# Controller.net
KiCad netlist of a schematic drawn in EAGLE
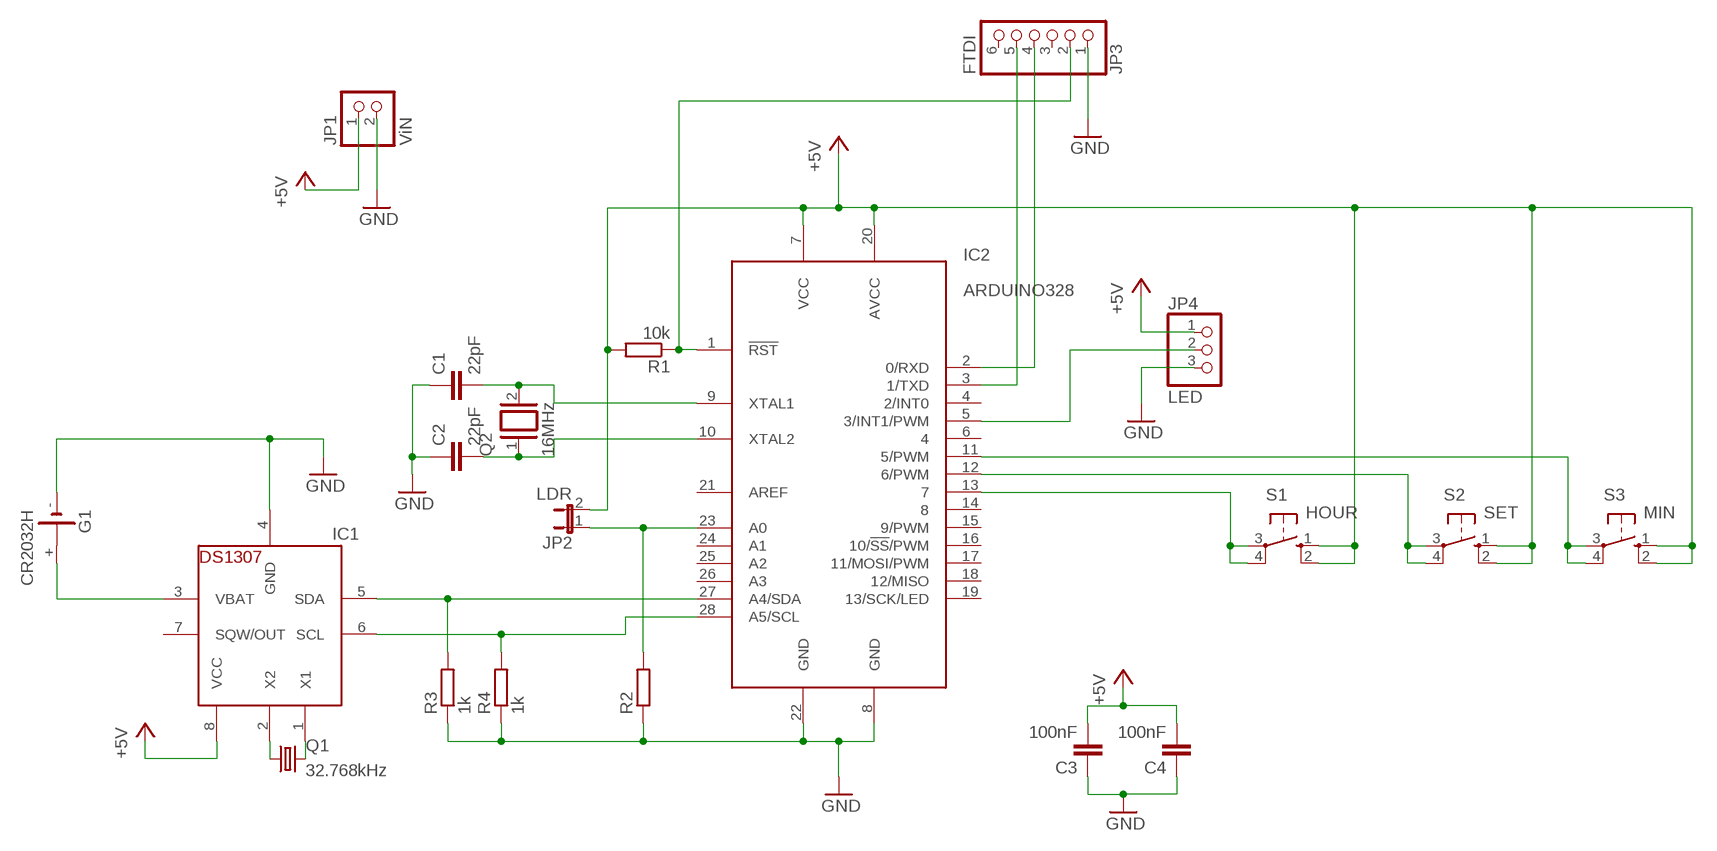
[diagram p0: schematic, sheet 1]

(export (version "E")
  (design (tool "Eeschema 10.0.6"))
  (components
    (comp (ref "C1")
      (value "22pF")
      (footprint "eagle-import:C025-024X044")
      (libsource (lib "eagle-import") (part "C-EU025-024X044"))
    )
    (comp (ref "C2")
      (value "22pF")
      (footprint "eagle-import:C025-024X044")
      (libsource (lib "eagle-import") (part "C-EU025-024X044"))
    )
    (comp (ref "C3")
      (value "100nF")
      (footprint "eagle-import:C025-024X044")
      (libsource (lib "eagle-import") (part "C-EU025-024X044"))
    )
    (comp (ref "C4")
      (value "100nF")
      (footprint "eagle-import:C025-024X044")
      (libsource (lib "eagle-import") (part "C-EU025-024X044"))
    )
    (comp (ref "G1")
      (value "CR2032H")
      (footprint "eagle-import:CR2032H")
      (libsource (lib "eagle-import") (part "CR2032H"))
    )
    (comp (ref "IC1")
      (value "DS1307")
      (footprint "eagle-import:DIL08")
      (libsource (lib "eagle-import") (part "DS1307"))
    )
    (comp (ref "IC2")
      (value "ARDUINO328")
      (footprint "eagle-import:DIP28")
      (libsource (lib "eagle-import") (part "ARDUINO328"))
    )
    (comp (ref "JP1")
      (value "ViN")
      (footprint "eagle-import:1X02")
      (libsource (lib "eagle-import") (part "PINHD-1X2"))
    )
    (comp (ref "JP2")
      (value "LDR")
      (footprint "eagle-import:JP1")
      (libsource (lib "eagle-import") (part "JP1E"))
    )
    (comp (ref "JP3")
      (value "FTDI")
      (footprint "eagle-import:1X06")
      (libsource (lib "eagle-import") (part "PINHD-1X6"))
    )
    (comp (ref "JP4")
      (value "LED")
      (footprint "eagle-import:1X03")
      (libsource (lib "eagle-import") (part "PINHD-1X3"))
    )
    (comp (ref "Q1")
      (value "32.768kHz")
      (footprint "eagle-import:TC26V")
      (libsource (lib "eagle-import") (part "CRYSTALTC26V"))
    )
    (comp (ref "Q2")
      (value "16MHz")
      (footprint "eagle-import:QS")
      (libsource (lib "eagle-import") (part "XTAL/S"))
    )
    (comp (ref "R1")
      (value "10k")
      (footprint "eagle-import:0204_5")
      (libsource (lib "eagle-import") (part "R-EU_0204/5"))
    )
    (comp (ref "R2")
      (value "R-EU_0204/5")
      (footprint "eagle-import:0204_5")
      (libsource (lib "eagle-import") (part "R-EU_0204/5"))
    )
    (comp (ref "R3")
      (value "1k")
      (footprint "eagle-import:0204_5")
      (libsource (lib "eagle-import") (part "R-EU_0204/5"))
    )
    (comp (ref "R4")
      (value "1k")
      (footprint "eagle-import:0204_5")
      (libsource (lib "eagle-import") (part "R-EU_0204/5"))
    )
    (comp (ref "S1")
      (value "HOUR")
      (footprint "eagle-import:B3F-10XX")
      (fields (field (name "MPN") "B3F-1000"))
      (libsource (lib "eagle-import") (part "10-XX"))
    )
    (comp (ref "S2")
      (value "SET")
      (footprint "eagle-import:B3F-10XX")
      (fields (field (name "MPN") "B3F-1000"))
      (libsource (lib "eagle-import") (part "10-XX"))
    )
    (comp (ref "S3")
      (value "MIN")
      (footprint "eagle-import:B3F-10XX")
      (fields (field (name "MPN") "B3F-1000"))
      (libsource (lib "eagle-import") (part "10-XX"))
    )
  )
  (nets
    (net (code "1") (name "+5V") (class "Default")
      (node (ref "C3") (pin "2") (pinfunction "2_2") (pintype "passive"))
      (node (ref "C4") (pin "2") (pinfunction "2_2") (pintype "passive"))
      (node (ref "IC1") (pin "8") (pinfunction "VCC_8") (pintype "power_in"))
      (node (ref "IC2") (pin "20") (pinfunction "AVCC_20") (pintype "bidirectional"))
      (node (ref "IC2") (pin "7") (pinfunction "VCC_7") (pintype "bidirectional"))
      (node (ref "JP1") (pin "1") (pinfunction "1_1") (pintype "passive"))
      (node (ref "JP2") (pin "2") (pinfunction "2_2") (pintype "passive"))
      (node (ref "JP4") (pin "1") (pinfunction "1_1") (pintype "passive"))
      (node (ref "R1") (pin "2") (pinfunction "2_2") (pintype "passive"))
      (node (ref "S1") (pin "1") (pinfunction "S_1") (pintype "passive"))
      (node (ref "S1") (pin "2") (pinfunction "S1_2") (pintype "passive"))
      (node (ref "S2") (pin "1") (pinfunction "S_1") (pintype "passive"))
      (node (ref "S2") (pin "2") (pinfunction "S1_2") (pintype "passive"))
      (node (ref "S3") (pin "1") (pinfunction "S_1") (pintype "passive"))
      (node (ref "S3") (pin "2") (pinfunction "S1_2") (pintype "passive"))
    )
    (net (code "2") (name "GND") (class "Default")
      (node (ref "C1") (pin "1") (pinfunction "1_1") (pintype "passive"))
      (node (ref "C2") (pin "1") (pinfunction "1_1") (pintype "passive"))
      (node (ref "C3") (pin "1") (pinfunction "1_1") (pintype "passive"))
      (node (ref "C4") (pin "1") (pinfunction "1_1") (pintype "passive"))
      (node (ref "G1") (pin "-") (pinfunction "-_-") (pintype "passive"))
      (node (ref "IC1") (pin "4") (pinfunction "GND_4") (pintype "power_in"))
      (node (ref "IC2") (pin "22") (pinfunction "GND_22") (pintype "bidirectional"))
      (node (ref "IC2") (pin "8") (pinfunction "GND_8") (pintype "bidirectional"))
      (node (ref "JP1") (pin "2") (pinfunction "2_2") (pintype "passive"))
      (node (ref "JP3") (pin "1") (pinfunction "1_1") (pintype "passive"))
      (node (ref "JP4") (pin "3") (pinfunction "3_3") (pintype "passive"))
      (node (ref "R2") (pin "1") (pinfunction "1_1") (pintype "passive"))
      (node (ref "R3") (pin "1") (pinfunction "1_1") (pintype "passive"))
      (node (ref "R4") (pin "1") (pinfunction "1_1") (pintype "passive"))
    )
    (net (code "3") (name "Net-(IC1-SCL)") (class "Default")
      (node (ref "IC1") (pin "6") (pinfunction "SCL_6") (pintype "bidirectional"))
      (node (ref "IC2") (pin "28") (pinfunction "A5/SCL_28") (pintype "bidirectional"))
      (node (ref "R4") (pin "2") (pinfunction "2_2") (pintype "passive"))
    )
    (net (code "4") (name "Net-(IC1-SDA)") (class "Default")
      (node (ref "IC1") (pin "5") (pinfunction "SDA_5") (pintype "bidirectional"))
      (node (ref "IC2") (pin "27") (pinfunction "A4/SDA_27") (pintype "bidirectional"))
      (node (ref "R3") (pin "2") (pinfunction "2_2") (pintype "passive"))
    )
    (net (code "5") (name "Net-(IC1-VBAT)") (class "Default")
      (node (ref "G1") (pin "+") (pinfunction "+_+") (pintype "passive"))
      (node (ref "IC1") (pin "3") (pinfunction "VBAT_3") (pintype "power_in"))
    )
    (net (code "6") (name "Net-(IC1-X1)") (class "Default")
      (node (ref "IC1") (pin "1") (pinfunction "X1_1") (pintype "passive"))
      (node (ref "Q1") (pin "2") (pinfunction "2_2") (pintype "passive"))
    )
    (net (code "7") (name "Net-(IC1-X2)") (class "Default")
      (node (ref "IC1") (pin "2") (pinfunction "X2_2") (pintype "passive"))
      (node (ref "Q1") (pin "1") (pinfunction "1_1") (pintype "passive"))
    )
    (net (code "8") (name "Net-(IC2-0{slash}RXD)") (class "Default")
      (node (ref "IC2") (pin "2") (pinfunction "0/RXD_2") (pintype "bidirectional"))
      (node (ref "JP3") (pin "4") (pinfunction "4_4") (pintype "passive"))
    )
    (net (code "9") (name "Net-(IC2-1{slash}TXD)") (class "Default")
      (node (ref "IC2") (pin "3") (pinfunction "1/TXD_3") (pintype "bidirectional"))
      (node (ref "JP3") (pin "5") (pinfunction "5_5") (pintype "passive"))
    )
    (net (code "10") (name "Net-(IC2-3{slash}INT1{slash}PWM)") (class "Default")
      (node (ref "IC2") (pin "5") (pinfunction "3/INT1/PWM_5") (pintype "bidirectional"))
      (node (ref "JP4") (pin "2") (pinfunction "2_2") (pintype "passive"))
    )
    (net (code "11") (name "Net-(IC2-5{slash}PWM)") (class "Default")
      (node (ref "IC2") (pin "11") (pinfunction "5/PWM_11") (pintype "bidirectional"))
      (node (ref "S3") (pin "3") (pinfunction "P_3") (pintype "passive"))
      (node (ref "S3") (pin "4") (pinfunction "P1_4") (pintype "passive"))
    )
    (net (code "12") (name "Net-(IC2-6{slash}PWM)") (class "Default")
      (node (ref "IC2") (pin "12") (pinfunction "6/PWM_12") (pintype "bidirectional"))
      (node (ref "S2") (pin "3") (pinfunction "P_3") (pintype "passive"))
      (node (ref "S2") (pin "4") (pinfunction "P1_4") (pintype "passive"))
    )
    (net (code "13") (name "Net-(IC2-7)") (class "Default")
      (node (ref "IC2") (pin "13") (pinfunction "7_13") (pintype "bidirectional"))
      (node (ref "S1") (pin "3") (pinfunction "P_3") (pintype "passive"))
      (node (ref "S1") (pin "4") (pinfunction "P1_4") (pintype "passive"))
    )
    (net (code "14") (name "Net-(IC2-A0)") (class "Default")
      (node (ref "IC2") (pin "23") (pinfunction "A0_23") (pintype "bidirectional"))
      (node (ref "JP2") (pin "1") (pinfunction "1_1") (pintype "passive"))
      (node (ref "R2") (pin "2") (pinfunction "2_2") (pintype "passive"))
    )
    (net (code "15") (name "Net-(IC2-XTAL1)") (class "Default")
      (node (ref "C1") (pin "2") (pinfunction "2_2") (pintype "passive"))
      (node (ref "IC2") (pin "9") (pinfunction "XTAL1_9") (pintype "bidirectional"))
      (node (ref "Q2") (pin "2") (pinfunction "2_2") (pintype "passive"))
    )
    (net (code "16") (name "Net-(IC2-XTAL2)") (class "Default")
      (node (ref "C2") (pin "2") (pinfunction "2_2") (pintype "passive"))
      (node (ref "IC2") (pin "10") (pinfunction "XTAL2_10") (pintype "bidirectional"))
      (node (ref "Q2") (pin "1") (pinfunction "1_1") (pintype "passive"))
    )
    (net (code "17") (name "Net-(IC2-~{RST})") (class "Default")
      (node (ref "IC2") (pin "1") (pinfunction "~{RST}_1") (pintype "bidirectional"))
      (node (ref "JP3") (pin "2") (pinfunction "2_2") (pintype "passive"))
      (node (ref "R1") (pin "1") (pinfunction "1_1") (pintype "passive"))
    )
    (net (code "18") (name "unconnected-(G1-+-Pad+@1)") (class "Default")
      (node (ref "G1") (pin "+@1") (pinfunction "+_+@1") (pintype "passive"))
    )
    (net (code "19") (name "unconnected-(IC1-SQW{slash}OUT-Pad7)") (class "Default")
      (node (ref "IC1") (pin "7") (pinfunction "SQW/OUT_7") (pintype "bidirectional"))
    )
    (net (code "20") (name "unconnected-(IC2-2{slash}INT0-Pad4)") (class "Default")
      (node (ref "IC2") (pin "4") (pinfunction "2/INT0_4") (pintype "bidirectional"))
    )
    (net (code "21") (name "unconnected-(IC2-4-Pad6)") (class "Default")
      (node (ref "IC2") (pin "6") (pinfunction "4_6") (pintype "bidirectional"))
    )
    (net (code "22") (name "unconnected-(IC2-8-Pad14)") (class "Default")
      (node (ref "IC2") (pin "14") (pinfunction "8_14") (pintype "bidirectional"))
    )
    (net (code "23") (name "unconnected-(IC2-9{slash}PWM-Pad15)") (class "Default")
      (node (ref "IC2") (pin "15") (pinfunction "9/PWM_15") (pintype "bidirectional"))
    )
    (net (code "24") (name "unconnected-(IC2-10{slash}~{SS}{slash}PWM-Pad16)") (class "Default")
      (node (ref "IC2") (pin "16") (pinfunction "10/~{SS}/PWM_16") (pintype "bidirectional"))
    )
    (net (code "25") (name "unconnected-(IC2-11{slash}MOSI{slash}PWM-Pad17)") (class "Default")
      (node (ref "IC2") (pin "17") (pinfunction "11/MOSI/PWM_17") (pintype "bidirectional"))
    )
    (net (code "26") (name "unconnected-(IC2-12{slash}MISO-Pad18)") (class "Default")
      (node (ref "IC2") (pin "18") (pinfunction "12/MISO_18") (pintype "bidirectional"))
    )
    (net (code "27") (name "unconnected-(IC2-13{slash}SCK{slash}LED-Pad19)") (class "Default")
      (node (ref "IC2") (pin "19") (pinfunction "13/SCK/LED_19") (pintype "bidirectional"))
    )
    (net (code "28") (name "unconnected-(IC2-A1-Pad24)") (class "Default")
      (node (ref "IC2") (pin "24") (pinfunction "A1_24") (pintype "bidirectional"))
    )
    (net (code "29") (name "unconnected-(IC2-A2-Pad25)") (class "Default")
      (node (ref "IC2") (pin "25") (pinfunction "A2_25") (pintype "bidirectional"))
    )
    (net (code "30") (name "unconnected-(IC2-A3-Pad26)") (class "Default")
      (node (ref "IC2") (pin "26") (pinfunction "A3_26") (pintype "bidirectional"))
    )
    (net (code "31") (name "unconnected-(IC2-AREF-Pad21)") (class "Default")
      (node (ref "IC2") (pin "21") (pinfunction "AREF_21") (pintype "bidirectional"))
    )
    (net (code "32") (name "unconnected-(JP3-Pad3)") (class "Default")
      (node (ref "JP3") (pin "3") (pinfunction "3_3") (pintype "passive"))
    )
    (net (code "33") (name "unconnected-(JP3-Pad6)") (class "Default")
      (node (ref "JP3") (pin "6") (pinfunction "6_6") (pintype "passive"))
    )
  )
)
